# SmartMatrix_V1.net
KiCad netlist of a schematic drawn in EAGLE
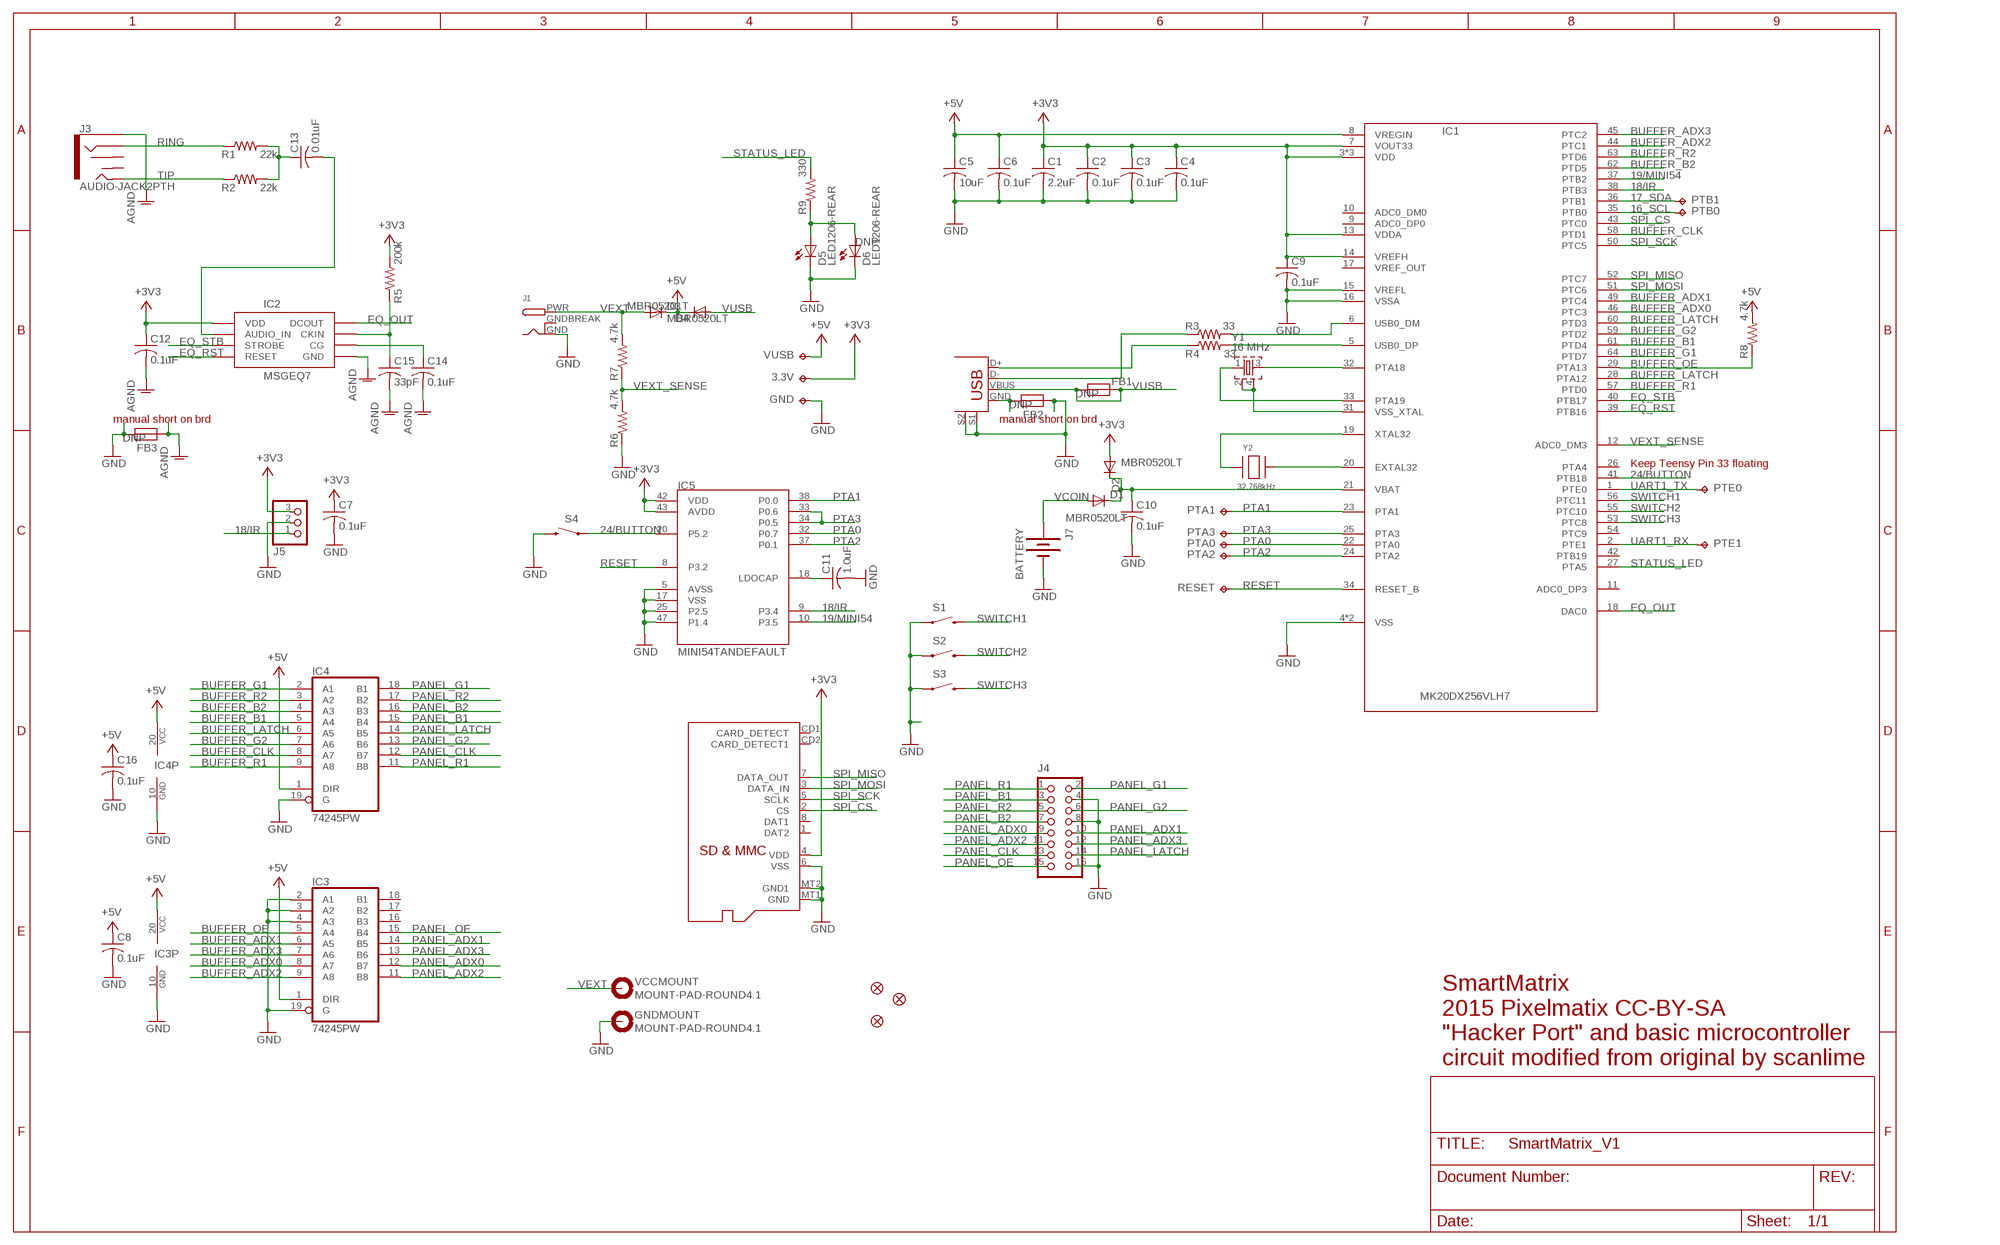
[diagram p0: schematic, sheet 1]

(export (version "E")
  (design (tool "Eeschema 10.0.6"))
  (components
    (comp (ref "3.3V")
      (value "TPTP18SQ")
      (footprint "eagle-import:TP18SQ")
      (libsource (lib "eagle-import") (part "TPTP18SQ"))
    )
    (comp (ref "C1")
      (value "2.2uF")
      (footprint "eagle-import:0805")
      (fields (field (name "PARTNO") "CAP CER 2.2UF 10V 10% X7R 0805"))
      (libsource (lib "eagle-import") (part "C-US0805/NO-OUTLINE"))
    )
    (comp (ref "C2")
      (value "0.1uF")
      (footprint "eagle-import:0805")
      (fields (field (name "PARTNO") "CAP CER 0.1UF 10V 10% X7R 0805"))
      (libsource (lib "eagle-import") (part "C-US0805/NO-OUTLINE"))
    )
    (comp (ref "C3")
      (value "0.1uF")
      (footprint "eagle-import:0805")
      (fields (field (name "PARTNO") "CAP CER 0.1UF 10V 10% X7R 0805"))
      (libsource (lib "eagle-import") (part "C-US0805/NO-OUTLINE"))
    )
    (comp (ref "C4")
      (value "0.1uF")
      (footprint "eagle-import:0805")
      (fields (field (name "PARTNO") "CAP CER 0.1UF 10V 10% X7R 0805"))
      (libsource (lib "eagle-import") (part "C-US0805/NO-OUTLINE"))
    )
    (comp (ref "C5")
      (value "10uF")
      (footprint "eagle-import:0805")
      (fields (field (name "PARTNO") "CAP CER 10UF 10V 10% X5R 0805"))
      (libsource (lib "eagle-import") (part "C-US0805/NO-OUTLINE"))
    )
    (comp (ref "C6")
      (value "0.1uF")
      (footprint "eagle-import:0805")
      (fields (field (name "PARTNO") "CAP CER 0.1UF 10V 10% X7R 0805"))
      (libsource (lib "eagle-import") (part "C-US0805/NO-OUTLINE"))
    )
    (comp (ref "C7")
      (value "0.1uF")
      (footprint "eagle-import:0805")
      (fields (field (name "PARTNO") "CAP CER 0.1UF 10V 10% X7R 0805"))
      (libsource (lib "eagle-import") (part "C-US0805/NO-OUTLINE"))
    )
    (comp (ref "C8")
      (value "0.1uF")
      (footprint "eagle-import:0805")
      (fields (field (name "PARTNO") "CAP CER 0.1UF 10V 10% X7R 0805"))
      (libsource (lib "eagle-import") (part "C-US0805/NO-OUTLINE"))
    )
    (comp (ref "C9")
      (value "0.1uF")
      (footprint "eagle-import:0805")
      (fields (field (name "PARTNO") "CAP CER 0.1UF 10V 10% X7R 0805"))
      (libsource (lib "eagle-import") (part "C-US0805/NO-OUTLINE"))
    )
    (comp (ref "C10")
      (value "0.1uF")
      (footprint "eagle-import:0805")
      (fields (field (name "PARTNO") "CAP CER 0.1UF 10V 10% X7R 0805"))
      (libsource (lib "eagle-import") (part "C-US0805/NO-OUTLINE"))
    )
    (comp (ref "C11")
      (value "1.0uF")
      (footprint "eagle-import:0805")
      (fields (field (name "PARTNO") "CAP CER 1UF 10V X7R 0805"))
      (libsource (lib "eagle-import") (part "C-US0805/NO-OUTLINE"))
    )
    (comp (ref "C12")
      (value "0.1uF")
      (footprint "eagle-import:0805")
      (fields (field (name "PARTNO") "CAP CER 0.1UF 10V 10% X7R 0805"))
      (libsource (lib "eagle-import") (part "C-US0805/NO-OUTLINE"))
    )
    (comp (ref "C13")
      (value "0.01uF")
      (footprint "eagle-import:0805")
      (fields (field (name "PARTNO") "CAP CER 10000PF 50V 10% X7R 0805"))
      (libsource (lib "eagle-import") (part "C-US0805/NO-OUTLINE"))
    )
    (comp (ref "C14")
      (value "0.1uF")
      (footprint "eagle-import:0805")
      (fields (field (name "PARTNO") "CAP CER 0.1UF 10V 10% X7R 0805"))
      (libsource (lib "eagle-import") (part "C-US0805/NO-OUTLINE"))
    )
    (comp (ref "C15")
      (value "33pF")
      (footprint "eagle-import:0805")
      (fields (field (name "PARTNO") "CAP CER 33PF 50V 5% NP0 0805"))
      (libsource (lib "eagle-import") (part "C-US0805/NO-OUTLINE"))
    )
    (comp (ref "C16")
      (value "0.1uF")
      (footprint "eagle-import:0805")
      (fields (field (name "PARTNO") "CAP CER 0.1UF 10V 10% X7R 0805"))
      (libsource (lib "eagle-import") (part "C-US0805/NO-OUTLINE"))
    )
    (comp (ref "D1")
      (value "MBR0520LT")
      (footprint "eagle-import:SOD123")
      (fields (field (name "PARTNO") "MBR0560-TP"))
      (libsource (lib "eagle-import") (part "MBR0520LT"))
    )
    (comp (ref "D2")
      (value "MBR0520LT")
      (footprint "eagle-import:SOD123")
      (fields (field (name "PARTNO") "MBR0560-TP"))
      (libsource (lib "eagle-import") (part "MBR0520LT"))
    )
    (comp (ref "D3")
      (value "MBR0520LT")
      (footprint "eagle-import:SOD123")
      (fields (field (name "PARTNO") "MBR0560-TP"))
      (libsource (lib "eagle-import") (part "MBR0520LT"))
    )
    (comp (ref "D4")
      (value "MBR0520LT")
      (footprint "eagle-import:SOD123")
      (fields (field (name "PARTNO") "MBR0560-TP"))
      (libsource (lib "eagle-import") (part "MBR0520LT"))
    )
    (comp (ref "D5")
      (value "LED1206-REAR")
      (footprint "eagle-import:LED-REARENTRY")
      (fields (field (name "PARTNO") "APTR3216YC"))
      (libsource (lib "eagle-import") (part "LED1206-REAR"))
    )
    (comp (ref "D6")
      (value "LED1206-REAR")
      (footprint "eagle-import:LED-REARENTRY")
      (libsource (lib "eagle-import") (part "LED1206-REAR"))
    )
    (comp (ref "FB1")
      (value "FB0805/NO-OUTLINE")
      (footprint "eagle-import:0805")
      (fields (field (name "PARTNO") "RES SMD 0.0 OHM JUMPER 1/8W 0805"))
      (libsource (lib "eagle-import") (part "FB0805/NO-OUTLINE"))
    )
    (comp (ref "FB2")
      (value "FB0805/NO-OUTLINE")
      (footprint "eagle-import:0805")
      (fields (field (name "PARTNO") "RES SMD 0.0 OHM JUMPER 1/8W 0805"))
      (libsource (lib "eagle-import") (part "FB0805/NO-OUTLINE"))
    )
    (comp (ref "FB3")
      (value "FB0805/NO-OUTLINE")
      (footprint "eagle-import:0805")
      (fields (field (name "PARTNO") "RES SMD 0.0 OHM JUMPER 1/8W 0805"))
      (libsource (lib "eagle-import") (part "FB0805/NO-OUTLINE"))
    )
    (comp (ref "FID1")
      (value "FIDUCIAL\"\"")
      (footprint "eagle-import:FIDUCIAL_1MM")
      (libsource (lib "eagle-import") (part "FIDUCIAL{dblquote}{dblquote}"))
    )
    (comp (ref "FID2")
      (value "FIDUCIAL\"\"")
      (footprint "eagle-import:FIDUCIAL_1MM")
      (libsource (lib "eagle-import") (part "FIDUCIAL{dblquote}{dblquote}"))
    )
    (comp (ref "FID3")
      (value "FIDUCIAL\"\"")
      (footprint "eagle-import:FIDUCIAL_1MM")
      (libsource (lib "eagle-import") (part "FIDUCIAL{dblquote}{dblquote}"))
    )
    (comp (ref "GND")
      (value "TPTP18SQ")
      (footprint "eagle-import:TP18SQ")
      (libsource (lib "eagle-import") (part "TPTP18SQ"))
    )
    (comp (ref "GNDMOUNT")
      (value "MOUNT-PAD-ROUND4.1")
      (footprint "eagle-import:4,1-PAD")
      (libsource (lib "eagle-import") (part "MOUNT-PAD-ROUND4.1"))
    )
    (comp (ref "IC1")
      (value "MK20DX256VLH7")
      (footprint "eagle-import:MK20DX256VLH7")
      (libsource (lib "eagle-import") (part "MK20DX256VLH7"))
    )
    (comp (ref "IC2")
      (value "MSGEQ7SOIC")
      (footprint "eagle-import:SOIC8")
      (fields (field (name "PARTNO") "MSGEQ7N"))
      (libsource (lib "eagle-import") (part "MSGEQ7SOIC"))
    )
    (comp (ref "IC3")
      (value "74245PW")
      (footprint "eagle-import:TSSOP-20")
      (fields (field (name "PARTNO") "SN74AHCT245PWR"))
      (libsource (lib "eagle-import") (part "74245PW"))
    )
    (comp (ref "IC4")
      (value "74245PW")
      (footprint "eagle-import:TSSOP-20")
      (fields (field (name "PARTNO") "SN74AHCT245PWR"))
      (libsource (lib "eagle-import") (part "74245PW"))
    )
    (comp (ref "IC5")
      (value "MINI54TANDEFAULT")
      (footprint "eagle-import:QFP50P900X900X160-48N")
      (libsource (lib "eagle-import") (part "MINI54TANDEFAULT"))
    )
    (comp (ref "J1")
      (value "DCBARRELPTH")
      (footprint "eagle-import:DCJACK_2MM_PTH")
      (fields (field (name "PARTNO") "PJ-002AH"))
      (libsource (lib "eagle-import") (part "DCBARRELPTH"))
    )
    (comp (ref "J2")
      (value "USB+SHIELD")
      (footprint "eagle-import:USB-B-PTH")
      (fields (field (name "PARTNO") "E8144-B02022-L"))
      (libsource (lib "eagle-import") (part "USB+SHIELD"))
    )
    (comp (ref "J3")
      (value "AUDIO-JACK2PTH")
      (footprint "eagle-import:AUDIO-JACK")
      (fields (field (name "PARTNO") "SJ1-3553NG"))
      (libsource (lib "eagle-import") (part "AUDIO-JACK2PTH"))
    )
    (comp (ref "J4")
      (value "CON_HEADER_2X08NOA")
      (footprint "eagle-import:2X08-NOA")
      (fields (field (name "PARTNO") "11149"))
      (libsource (lib "eagle-import") (part "CON_HEADER_2X08NOA"))
    )
    (comp (ref "J5")
      (value "CON_HEADER_1X03SMD/90-NOA")
      (footprint "eagle-import:1X03-SMD_90-NOA")
      (fields (field (name "PARTNO") "11182"))
      (libsource (lib "eagle-import") (part "CON_HEADER_1X03SMD/90-NOA"))
    )
    (comp (ref "J6")
      (value "MICROSD")
      (footprint "eagle-import:MICROSD")
      (fields (field (name "PARTNO") "101-00660-68-6"))
      (libsource (lib "eagle-import") (part "MICROSD"))
    )
    (comp (ref "J7")
      (value "BATTERY")
      (footprint "eagle-import:BU2032-SM")
      (fields (field (name "PARTNO") "05581"))
      (libsource (lib "eagle-import") (part "BATTERY"))
    )
    (comp (ref "PTA0")
      (value "TPTP18SQ")
      (footprint "eagle-import:TP18SQ")
      (libsource (lib "eagle-import") (part "TPTP18SQ"))
    )
    (comp (ref "PTA1")
      (value "TPTP18SQ")
      (footprint "eagle-import:TP18SQ")
      (libsource (lib "eagle-import") (part "TPTP18SQ"))
    )
    (comp (ref "PTA2")
      (value "TPTP18SQ")
      (footprint "eagle-import:TP18SQ")
      (libsource (lib "eagle-import") (part "TPTP18SQ"))
    )
    (comp (ref "PTA3")
      (value "TPTP18SQ")
      (footprint "eagle-import:TP18SQ")
      (libsource (lib "eagle-import") (part "TPTP18SQ"))
    )
    (comp (ref "PTB0")
      (value "TPTP18SQ")
      (footprint "eagle-import:TP18SQ")
      (libsource (lib "eagle-import") (part "TPTP18SQ"))
    )
    (comp (ref "PTB1")
      (value "TPTP18SQ")
      (footprint "eagle-import:TP18SQ")
      (libsource (lib "eagle-import") (part "TPTP18SQ"))
    )
    (comp (ref "PTE0")
      (value "TPTP18SQ")
      (footprint "eagle-import:TP18SQ")
      (libsource (lib "eagle-import") (part "TPTP18SQ"))
    )
    (comp (ref "PTE1")
      (value "TPTP18SQ")
      (footprint "eagle-import:TP18SQ")
      (libsource (lib "eagle-import") (part "TPTP18SQ"))
    )
    (comp (ref "R1")
      (value "22k")
      (footprint "eagle-import:0805")
      (fields (field (name "PARTNO") "RES SMD 22K OHM 5% 1/8W 0805"))
      (libsource (lib "eagle-import") (part "R-US_0805/NO-OUTLINE"))
    )
    (comp (ref "R2")
      (value "22k")
      (footprint "eagle-import:0805")
      (fields (field (name "PARTNO") "RES SMD 22K OHM 5% 1/8W 0805"))
      (libsource (lib "eagle-import") (part "R-US_0805/NO-OUTLINE"))
    )
    (comp (ref "R3")
      (value "33")
      (footprint "eagle-import:0805")
      (fields (field (name "PARTNO") "RES 33 OHM 1/8W 5% 0805 SMD"))
      (libsource (lib "eagle-import") (part "R-US_0805/NO-OUTLINE"))
    )
    (comp (ref "R4")
      (value "33")
      (footprint "eagle-import:0805")
      (fields (field (name "PARTNO") "RES 33 OHM 1/8W 5% 0805 SMD"))
      (libsource (lib "eagle-import") (part "R-US_0805/NO-OUTLINE"))
    )
    (comp (ref "R5")
      (value "200k")
      (footprint "eagle-import:0805")
      (fields (field (name "PARTNO") "RES SMD 200K OHM 5% 1/8W 0805"))
      (libsource (lib "eagle-import") (part "R-US_0805/NO-OUTLINE"))
    )
    (comp (ref "R6")
      (value "4.7k")
      (footprint "eagle-import:0805")
      (fields (field (name "PARTNO") "RES SMD 4.7K OHM 5% 1/8W 0805"))
      (libsource (lib "eagle-import") (part "R-US_0805/NO-OUTLINE"))
    )
    (comp (ref "R7")
      (value "4.7k")
      (footprint "eagle-import:0805")
      (fields (field (name "PARTNO") "RES SMD 4.7K OHM 5% 1/8W 0805"))
      (libsource (lib "eagle-import") (part "R-US_0805/NO-OUTLINE"))
    )
    (comp (ref "R8")
      (value "4.7k")
      (footprint "eagle-import:0805")
      (fields (field (name "PARTNO") "RES SMD 4.7K OHM 5% 1/8W 0805"))
      (libsource (lib "eagle-import") (part "R-US_0805/NO-OUTLINE"))
    )
    (comp (ref "R9")
      (value "330")
      (footprint "eagle-import:0805")
      (fields (field (name "PARTNO") "RES SMD 330 OHM 5% 1/8W 0805"))
      (libsource (lib "eagle-import") (part "R-US_0805/NO-OUTLINE"))
    )
    (comp (ref "RESET")
      (value "TPTP18SQ")
      (footprint "eagle-import:TP18SQ")
      (libsource (lib "eagle-import") (part "TPTP18SQ"))
    )
    (comp (ref "S1")
      (value "SWITCH-MOMENTARY-2PTH")
      (footprint "eagle-import:TACTILE-PTH")
      (libsource (lib "eagle-import") (part "SWITCH-MOMENTARY-2PTH"))
    )
    (comp (ref "S2")
      (value "SWITCH-MOMENTARY-2PTH")
      (footprint "eagle-import:TACTILE-PTH")
      (libsource (lib "eagle-import") (part "SWITCH-MOMENTARY-2PTH"))
    )
    (comp (ref "S3")
      (value "SWITCH-MOMENTARY-2PTH")
      (footprint "eagle-import:TACTILE-PTH")
      (libsource (lib "eagle-import") (part "SWITCH-MOMENTARY-2PTH"))
    )
    (comp (ref "S4")
      (value "SWITCH-MOMENTARY-2PTH")
      (footprint "eagle-import:TACTILE-PTH")
      (libsource (lib "eagle-import") (part "SWITCH-MOMENTARY-2PTH"))
    )
    (comp (ref "VCCMOUNT")
      (value "MOUNT-PAD-ROUND4.1")
      (footprint "eagle-import:4,1-PAD")
      (libsource (lib "eagle-import") (part "MOUNT-PAD-ROUND4.1"))
    )
    (comp (ref "VUSB")
      (value "TPTP18SQ")
      (footprint "eagle-import:TP18SQ")
      (libsource (lib "eagle-import") (part "TPTP18SQ"))
    )
    (comp (ref "Y1")
      (value "16 MHz")
      (footprint "eagle-import:TSX-3225")
      (fields (field (name "PARTNO") "TSX-3225 16.0000MF09Z-AC3"))
      (libsource (lib "eagle-import") (part "TSX-32250"))
    )
    (comp (ref "Y2")
      (value "32.768kHz")
      (footprint "eagle-import:XTAL3215")
      (fields (field (name "PARTNO") "9HT10-32.768KDZF-T"))
      (libsource (lib "eagle-import") (part "XTAL-3.2X1.5"))
    )
  )
  (nets
    (net (code "1") (name "+3V3") (class "Default")
      (node (ref "3.3V") (pin "TP") (pinfunction "TP_TP") (pintype "input"))
      (node (ref "C1") (pin "1") (pinfunction "1_1") (pintype "passive"))
      (node (ref "C12") (pin "1") (pinfunction "1_1") (pintype "passive"))
      (node (ref "C2") (pin "1") (pinfunction "1_1") (pintype "passive"))
      (node (ref "C3") (pin "1") (pinfunction "1_1") (pintype "passive"))
      (node (ref "C4") (pin "1") (pinfunction "1_1") (pintype "passive"))
      (node (ref "C7") (pin "1") (pinfunction "1_1") (pintype "passive"))
      (node (ref "C9") (pin "1") (pinfunction "1_1") (pintype "passive"))
      (node (ref "D2") (pin "A") (pinfunction "A_A") (pintype "passive"))
      (node (ref "IC1") (pin "13") (pinfunction "VDDA_13") (pintype "bidirectional"))
      (node (ref "IC1") (pin "14") (pinfunction "VREFH_14") (pintype "bidirectional"))
      (node (ref "IC1") (pin "3") (pinfunction "VDD_3") (pintype "bidirectional"))
      (node (ref "IC1") (pin "30") (pinfunction "VDD_30") (pintype "bidirectional"))
      (node (ref "IC1") (pin "48") (pinfunction "VDD_48") (pintype "bidirectional"))
      (node (ref "IC1") (pin "7") (pinfunction "VOUT33_7") (pintype "bidirectional"))
      (node (ref "IC2") (pin "1") (pinfunction "VDD_1") (pintype "input"))
      (node (ref "IC5") (pin "42") (pinfunction "VDD_42") (pintype "bidirectional"))
      (node (ref "IC5") (pin "43") (pinfunction "AVDD_43") (pintype "bidirectional"))
      (node (ref "J5") (pin "3") (pinfunction "3_3") (pintype "passive"))
      (node (ref "J6") (pin "4") (pinfunction "VDD_4") (pintype "power_in"))
      (node (ref "R5") (pin "2") (pinfunction "2_2") (pintype "passive"))
    )
    (net (code "2") (name "+5V") (class "Default")
      (node (ref "C16") (pin "1") (pinfunction "1_1") (pintype "passive"))
      (node (ref "C5") (pin "1") (pinfunction "1_1") (pintype "passive"))
      (node (ref "C6") (pin "1") (pinfunction "1_1") (pintype "passive"))
      (node (ref "C8") (pin "1") (pinfunction "1_1") (pintype "passive"))
      (node (ref "D3") (pin "C") (pinfunction "C_C") (pintype "passive"))
      (node (ref "D4") (pin "C") (pinfunction "C_C") (pintype "passive"))
      (node (ref "IC1") (pin "8") (pinfunction "VREGIN_8") (pintype "bidirectional"))
      (node (ref "IC3") (pin "1") (pinfunction "DIR_1") (pintype "input"))
      (node (ref "IC3") (pin "20") (pinfunction "VCC_20") (pintype "power_in"))
      (node (ref "IC4") (pin "1") (pinfunction "DIR_1") (pintype "input"))
      (node (ref "IC4") (pin "20") (pinfunction "VCC_20") (pintype "power_in"))
      (node (ref "R8") (pin "2") (pinfunction "2_2") (pintype "passive"))
      (node (ref "VUSB") (pin "TP") (pinfunction "TP_TP") (pintype "input"))
    )
    (net (code "3") (name "/16_SCL") (class "Default")
      (node (ref "IC1") (pin "35") (pinfunction "PTB0_35") (pintype "bidirectional"))
      (node (ref "PTB0") (pin "TP") (pinfunction "TP_TP") (pintype "input"))
    )
    (net (code "4") (name "/17_SDA") (class "Default")
      (node (ref "IC1") (pin "36") (pinfunction "PTB1_36") (pintype "bidirectional"))
      (node (ref "PTB1") (pin "TP") (pinfunction "TP_TP") (pintype "input"))
    )
    (net (code "5") (name "/18{slash}IR") (class "Default")
      (node (ref "IC1") (pin "38") (pinfunction "PTB3_38") (pintype "bidirectional"))
      (node (ref "IC5") (pin "9") (pinfunction "P3.4_9") (pintype "bidirectional"))
      (node (ref "J5") (pin "1") (pinfunction "1_1") (pintype "passive"))
    )
    (net (code "6") (name "/19{slash}MINI54") (class "Default")
      (node (ref "IC1") (pin "37") (pinfunction "PTB2_37") (pintype "bidirectional"))
      (node (ref "IC5") (pin "10") (pinfunction "P3.5_10") (pintype "bidirectional"))
    )
    (net (code "7") (name "/24{slash}BUTTON") (class "Default")
      (node (ref "IC1") (pin "41") (pinfunction "PTB18_41") (pintype "bidirectional"))
      (node (ref "IC5") (pin "20") (pinfunction "P5.2_20") (pintype "bidirectional"))
      (node (ref "S4") (pin "1") (pinfunction "1_1") (pintype "passive"))
    )
    (net (code "8") (name "/BUFFER_ADX0") (class "Default")
      (node (ref "IC1") (pin "46") (pinfunction "PTC3_46") (pintype "bidirectional"))
      (node (ref "IC3") (pin "8") (pinfunction "A7_8") (pintype "bidirectional"))
    )
    (net (code "9") (name "/BUFFER_ADX1") (class "Default")
      (node (ref "IC1") (pin "49") (pinfunction "PTC4_49") (pintype "bidirectional"))
      (node (ref "IC3") (pin "6") (pinfunction "A5_6") (pintype "bidirectional"))
    )
    (net (code "10") (name "/BUFFER_ADX2") (class "Default")
      (node (ref "IC1") (pin "44") (pinfunction "PTC1_44") (pintype "bidirectional"))
      (node (ref "IC3") (pin "9") (pinfunction "A8_9") (pintype "bidirectional"))
    )
    (net (code "11") (name "/BUFFER_ADX3") (class "Default")
      (node (ref "IC1") (pin "45") (pinfunction "PTC2_45") (pintype "bidirectional"))
      (node (ref "IC3") (pin "7") (pinfunction "A6_7") (pintype "bidirectional"))
    )
    (net (code "12") (name "/BUFFER_B1") (class "Default")
      (node (ref "IC1") (pin "61") (pinfunction "PTD4_61") (pintype "bidirectional"))
      (node (ref "IC4") (pin "5") (pinfunction "A4_5") (pintype "bidirectional"))
    )
    (net (code "13") (name "/BUFFER_B2") (class "Default")
      (node (ref "IC1") (pin "62") (pinfunction "PTD5_62") (pintype "bidirectional"))
      (node (ref "IC4") (pin "4") (pinfunction "A3_4") (pintype "bidirectional"))
    )
    (net (code "14") (name "/BUFFER_CLK") (class "Default")
      (node (ref "IC1") (pin "58") (pinfunction "PTD1_58") (pintype "bidirectional"))
      (node (ref "IC4") (pin "8") (pinfunction "A7_8") (pintype "bidirectional"))
    )
    (net (code "15") (name "/BUFFER_G1") (class "Default")
      (node (ref "IC1") (pin "64") (pinfunction "PTD7_64") (pintype "bidirectional"))
      (node (ref "IC4") (pin "2") (pinfunction "A1_2") (pintype "bidirectional"))
    )
    (net (code "16") (name "/BUFFER_G2") (class "Default")
      (node (ref "IC1") (pin "59") (pinfunction "PTD2_59") (pintype "bidirectional"))
      (node (ref "IC4") (pin "7") (pinfunction "A6_7") (pintype "bidirectional"))
    )
    (net (code "17") (name "/BUFFER_LATCH") (class "Default")
      (node (ref "IC1") (pin "28") (pinfunction "PTA12_28") (pintype "bidirectional"))
      (node (ref "IC1") (pin "60") (pinfunction "PTD3_60") (pintype "bidirectional"))
      (node (ref "IC4") (pin "6") (pinfunction "A5_6") (pintype "bidirectional"))
    )
    (net (code "18") (name "/BUFFER_OE") (class "Default")
      (node (ref "IC1") (pin "29") (pinfunction "PTA13_29") (pintype "bidirectional"))
      (node (ref "IC3") (pin "5") (pinfunction "A4_5") (pintype "bidirectional"))
      (node (ref "R8") (pin "1") (pinfunction "1_1") (pintype "passive"))
    )
    (net (code "19") (name "/BUFFER_R1") (class "Default")
      (node (ref "IC1") (pin "57") (pinfunction "PTD0_57") (pintype "bidirectional"))
      (node (ref "IC4") (pin "9") (pinfunction "A8_9") (pintype "bidirectional"))
    )
    (net (code "20") (name "/BUFFER_R2") (class "Default")
      (node (ref "IC1") (pin "63") (pinfunction "PTD6_63") (pintype "bidirectional"))
      (node (ref "IC4") (pin "3") (pinfunction "A2_3") (pintype "bidirectional"))
    )
    (net (code "21") (name "/EQ_OUT") (class "Default")
      (node (ref "IC1") (pin "18") (pinfunction "DAC0_18") (pintype "bidirectional"))
      (node (ref "IC2") (pin "3") (pinfunction "DCOUT_3") (pintype "bidirectional"))
    )
    (net (code "22") (name "/EQ_RST") (class "Default")
      (node (ref "IC1") (pin "39") (pinfunction "PTB16_39") (pintype "bidirectional"))
      (node (ref "IC2") (pin "7") (pinfunction "RESET_7") (pintype "input"))
    )
    (net (code "23") (name "/EQ_STB") (class "Default")
      (node (ref "IC1") (pin "40") (pinfunction "PTB17_40") (pintype "bidirectional"))
      (node (ref "IC2") (pin "4") (pinfunction "STROBE_4") (pintype "input"))
    )
    (net (code "24") (name "/GNDBREAK") (class "Default")
      (node (ref "J1") (pin "GNDBREAK") (pinfunction "GNDBREAK_GNDBREAK") (pintype "power_in"))
    )
    (net (code "25") (name "/PANEL_ADX0") (class "Default")
      (node (ref "IC3") (pin "12") (pinfunction "B7_12") (pintype "bidirectional"))
      (node (ref "J4") (pin "9") (pinfunction "9_9") (pintype "passive"))
    )
    (net (code "26") (name "/PANEL_ADX1") (class "Default")
      (node (ref "IC3") (pin "14") (pinfunction "B5_14") (pintype "bidirectional"))
      (node (ref "J4") (pin "10") (pinfunction "10_10") (pintype "passive"))
    )
    (net (code "27") (name "/PANEL_ADX2") (class "Default")
      (node (ref "IC3") (pin "11") (pinfunction "B8_11") (pintype "bidirectional"))
      (node (ref "J4") (pin "11") (pinfunction "11_11") (pintype "passive"))
    )
    (net (code "28") (name "/PANEL_ADX3") (class "Default")
      (node (ref "IC3") (pin "13") (pinfunction "B6_13") (pintype "bidirectional"))
      (node (ref "J4") (pin "12") (pinfunction "12_12") (pintype "passive"))
    )
    (net (code "29") (name "/PANEL_B1") (class "Default")
      (node (ref "IC4") (pin "15") (pinfunction "B4_15") (pintype "bidirectional"))
      (node (ref "J4") (pin "3") (pinfunction "3_3") (pintype "passive"))
    )
    (net (code "30") (name "/PANEL_B2") (class "Default")
      (node (ref "IC4") (pin "16") (pinfunction "B3_16") (pintype "bidirectional"))
      (node (ref "J4") (pin "7") (pinfunction "7_7") (pintype "passive"))
    )
    (net (code "31") (name "/PANEL_CLK") (class "Default")
      (node (ref "IC4") (pin "12") (pinfunction "B7_12") (pintype "bidirectional"))
      (node (ref "J4") (pin "13") (pinfunction "13_13") (pintype "passive"))
    )
    (net (code "32") (name "/PANEL_G1") (class "Default")
      (node (ref "IC4") (pin "18") (pinfunction "B1_18") (pintype "bidirectional"))
      (node (ref "J4") (pin "2") (pinfunction "2_2") (pintype "passive"))
    )
    (net (code "33") (name "/PANEL_G2") (class "Default")
      (node (ref "IC4") (pin "13") (pinfunction "B6_13") (pintype "bidirectional"))
      (node (ref "J4") (pin "6") (pinfunction "6_6") (pintype "passive"))
    )
    (net (code "34") (name "/PANEL_LATCH") (class "Default")
      (node (ref "IC4") (pin "14") (pinfunction "B5_14") (pintype "bidirectional"))
      (node (ref "J4") (pin "14") (pinfunction "14_14") (pintype "passive"))
    )
    (net (code "35") (name "/PANEL_OE") (class "Default")
      (node (ref "IC3") (pin "15") (pinfunction "B4_15") (pintype "bidirectional"))
      (node (ref "J4") (pin "15") (pinfunction "15_15") (pintype "passive"))
    )
    (net (code "36") (name "/PANEL_R1") (class "Default")
      (node (ref "IC4") (pin "11") (pinfunction "B8_11") (pintype "bidirectional"))
      (node (ref "J4") (pin "1") (pinfunction "1_1") (pintype "passive"))
    )
    (net (code "37") (name "/PANEL_R2") (class "Default")
      (node (ref "IC4") (pin "17") (pinfunction "B2_17") (pintype "bidirectional"))
      (node (ref "J4") (pin "5") (pinfunction "5_5") (pintype "passive"))
    )
    (net (code "38") (name "/PTA0") (class "Default")
      (node (ref "IC1") (pin "22") (pinfunction "PTA0_22") (pintype "bidirectional"))
      (node (ref "IC5") (pin "32") (pinfunction "P0.7_32") (pintype "bidirectional"))
      (node (ref "PTA0") (pin "TP") (pinfunction "TP_TP") (pintype "input"))
    )
    (net (code "39") (name "/PTA1") (class "Default")
      (node (ref "IC1") (pin "23") (pinfunction "PTA1_23") (pintype "bidirectional"))
      (node (ref "IC5") (pin "38") (pinfunction "P0.0_38") (pintype "bidirectional"))
      (node (ref "PTA1") (pin "TP") (pinfunction "TP_TP") (pintype "input"))
    )
    (net (code "40") (name "/PTA2") (class "Default")
      (node (ref "IC1") (pin "24") (pinfunction "PTA2_24") (pintype "bidirectional"))
      (node (ref "IC5") (pin "37") (pinfunction "P0.1_37") (pintype "bidirectional"))
      (node (ref "PTA2") (pin "TP") (pinfunction "TP_TP") (pintype "input"))
    )
    (net (code "41") (name "/PTA3") (class "Default")
      (node (ref "IC1") (pin "25") (pinfunction "PTA3_25") (pintype "bidirectional"))
      (node (ref "IC5") (pin "33") (pinfunction "P0.6_33") (pintype "bidirectional"))
      (node (ref "IC5") (pin "34") (pinfunction "P0.5_34") (pintype "bidirectional"))
      (node (ref "PTA3") (pin "TP") (pinfunction "TP_TP") (pintype "input"))
    )
    (net (code "42") (name "/RESET") (class "Default")
      (node (ref "IC1") (pin "34") (pinfunction "RESET_B_34") (pintype "bidirectional"))
      (node (ref "IC5") (pin "8") (pinfunction "P3.2_8") (pintype "bidirectional"))
      (node (ref "RESET") (pin "TP") (pinfunction "TP_TP") (pintype "input"))
    )
    (net (code "43") (name "/RING") (class "Default")
      (node (ref "J3") (pin "RING") (pinfunction "RING_RING") (pintype "bidirectional"))
      (node (ref "R1") (pin "1") (pinfunction "1_1") (pintype "passive"))
    )
    (net (code "44") (name "/SPI_CS") (class "Default")
      (node (ref "IC1") (pin "43") (pinfunction "PTC0_43") (pintype "bidirectional"))
      (node (ref "J6") (pin "2") (pinfunction "CS_2") (pintype "input"))
    )
    (net (code "45") (name "/SPI_MISO") (class "Default")
      (node (ref "IC1") (pin "52") (pinfunction "PTC7_52") (pintype "bidirectional"))
      (node (ref "J6") (pin "7") (pinfunction "DATA_OUT_7") (pintype "output"))
    )
    (net (code "46") (name "/SPI_MOSI") (class "Default")
      (node (ref "IC1") (pin "51") (pinfunction "PTC6_51") (pintype "bidirectional"))
      (node (ref "J6") (pin "3") (pinfunction "DATA_IN_3") (pintype "input"))
    )
    (net (code "47") (name "/SPI_SCK") (class "Default")
      (node (ref "IC1") (pin "50") (pinfunction "PTC5_50") (pintype "bidirectional"))
      (node (ref "J6") (pin "5") (pinfunction "SCLK_5") (pintype "input"))
    )
    (net (code "48") (name "/STATUS_LED") (class "Default")
      (node (ref "IC1") (pin "27") (pinfunction "PTA5_27") (pintype "bidirectional"))
      (node (ref "R9") (pin "2") (pinfunction "2_2") (pintype "passive"))
    )
    (net (code "49") (name "/SWITCH1") (class "Default")
      (node (ref "IC1") (pin "56") (pinfunction "PTC11_56") (pintype "bidirectional"))
      (node (ref "S1") (pin "3") (pinfunction "2_3") (pintype "passive"))
    )
    (net (code "50") (name "/SWITCH2") (class "Default")
      (node (ref "IC1") (pin "55") (pinfunction "PTC10_55") (pintype "bidirectional"))
      (node (ref "S2") (pin "3") (pinfunction "2_3") (pintype "passive"))
    )
    (net (code "51") (name "/SWITCH3") (class "Default")
      (node (ref "IC1") (pin "53") (pinfunction "PTC8_53") (pintype "bidirectional"))
      (node (ref "S3") (pin "3") (pinfunction "2_3") (pintype "passive"))
    )
    (net (code "52") (name "/TIP") (class "Default")
      (node (ref "J3") (pin "TIP") (pinfunction "TIP_TIP") (pintype "bidirectional"))
      (node (ref "R2") (pin "1") (pinfunction "1_1") (pintype "passive"))
    )
    (net (code "53") (name "/UART1_RX") (class "Default")
      (node (ref "IC1") (pin "2") (pinfunction "PTE1_2") (pintype "bidirectional"))
      (node (ref "PTE1") (pin "TP") (pinfunction "TP_TP") (pintype "input"))
    )
    (net (code "54") (name "/UART1_TX") (class "Default")
      (node (ref "IC1") (pin "1") (pinfunction "PTE0_1") (pintype "bidirectional"))
      (node (ref "PTE0") (pin "TP") (pinfunction "TP_TP") (pintype "input"))
    )
    (net (code "55") (name "/VCOIN") (class "Default")
      (node (ref "D1") (pin "A") (pinfunction "A_A") (pintype "passive"))
      (node (ref "J7") (pin "+") (pinfunction "+_+") (pintype "power_in"))
    )
    (net (code "56") (name "/VEXT") (class "Default")
      (node (ref "D3") (pin "A") (pinfunction "A_A") (pintype "passive"))
      (node (ref "J1") (pin "PWR") (pinfunction "PWR_PWR") (pintype "power_in"))
      (node (ref "R7") (pin "2") (pinfunction "2_2") (pintype "passive"))
      (node (ref "VCCMOUNT") (pin "B4,1") (pinfunction "MOUNT_B4,1") (pintype "passive"))
    )
    (net (code "57") (name "/VEXT_SENSE") (class "Default")
      (node (ref "IC1") (pin "12") (pinfunction "ADC0_DM3_12") (pintype "bidirectional"))
      (node (ref "R6") (pin "2") (pinfunction "2_2") (pintype "passive"))
      (node (ref "R7") (pin "1") (pinfunction "1_1") (pintype "passive"))
    )
    (net (code "58") (name "/VUSB") (class "Default")
      (node (ref "D4") (pin "A") (pinfunction "A_A") (pintype "passive"))
      (node (ref "FB1") (pin "1") (pinfunction "P$1_1") (pintype "bidirectional"))
      (node (ref "FB1") (pin "2") (pinfunction "P$2_2") (pintype "bidirectional"))
      (node (ref "J2") (pin "VBUS") (pinfunction "VBUS_VBUS") (pintype "bidirectional"))
    )
    (net (code "59") (name "AGND") (class "Default")
      (node (ref "C12") (pin "2") (pinfunction "2_2") (pintype "passive"))
      (node (ref "C14") (pin "2") (pinfunction "2_2") (pintype "passive"))
      (node (ref "C15") (pin "2") (pinfunction "2_2") (pintype "passive"))
      (node (ref "FB3") (pin "2") (pinfunction "P$2_2") (pintype "bidirectional"))
      (node (ref "IC2") (pin "2") (pinfunction "GND_2") (pintype "bidirectional"))
      (node (ref "J3") (pin "SLEEVE") (pinfunction "SLEEVE_SLEEVE") (pintype "bidirectional"))
    )
    (net (code "60") (name "GND") (class "Default")
      (node (ref "C1") (pin "2") (pinfunction "2_2") (pintype "passive"))
      (node (ref "C10") (pin "2") (pinfunction "2_2") (pintype "passive"))
      (node (ref "C11") (pin "2") (pinfunction "2_2") (pintype "passive"))
      (node (ref "C16") (pin "2") (pinfunction "2_2") (pintype "passive"))
      (node (ref "C2") (pin "2") (pinfunction "2_2") (pintype "passive"))
      (node (ref "C3") (pin "2") (pinfunction "2_2") (pintype "passive"))
      (node (ref "C4") (pin "2") (pinfunction "2_2") (pintype "passive"))
      (node (ref "C5") (pin "2") (pinfunction "2_2") (pintype "passive"))
      (node (ref "C6") (pin "2") (pinfunction "2_2") (pintype "passive"))
      (node (ref "C7") (pin "2") (pinfunction "2_2") (pintype "passive"))
      (node (ref "C8") (pin "2") (pinfunction "2_2") (pintype "passive"))
      (node (ref "C9") (pin "2") (pinfunction "2_2") (pintype "passive"))
      (node (ref "D5") (pin "-") (pinfunction "C_-") (pintype "passive"))
      (node (ref "D6") (pin "-") (pinfunction "C_-") (pintype "passive"))
      (node (ref "FB2") (pin "2") (pinfunction "P$2_2") (pintype "bidirectional"))
      (node (ref "FB3") (pin "1") (pinfunction "P$1_1") (pintype "bidirectional"))
      (node (ref "GND") (pin "TP") (pinfunction "TP_TP") (pintype "input"))
      (node (ref "GNDMOUNT") (pin "B4,1") (pinfunction "MOUNT_B4,1") (pintype "passive"))
      (node (ref "IC1") (pin "15") (pinfunction "VREFL_15") (pintype "bidirectional"))
      (node (ref "IC1") (pin "16") (pinfunction "VSSA_16") (pintype "bidirectional"))
      (node (ref "IC1") (pin "4") (pinfunction "VSS_4") (pintype "bidirectional"))
      (node (ref "IC1") (pin "47") (pinfunction "VSS_47") (pintype "bidirectional"))
      (node (ref "IC3") (pin "10") (pinfunction "GND_10") (pintype "power_in"))
      (node (ref "IC3") (pin "19") (pinfunction "G_19") (pintype "input"))
      (node (ref "IC3") (pin "2") (pinfunction "A1_2") (pintype "bidirectional"))
      (node (ref "IC3") (pin "3") (pinfunction "A2_3") (pintype "bidirectional"))
      (node (ref "IC3") (pin "4") (pinfunction "A3_4") (pintype "bidirectional"))
      (node (ref "IC4") (pin "10") (pinfunction "GND_10") (pintype "power_in"))
      (node (ref "IC4") (pin "19") (pinfunction "G_19") (pintype "input"))
      (node (ref "IC5") (pin "17") (pinfunction "VSS_17") (pintype "bidirectional"))
      (node (ref "IC5") (pin "25") (pinfunction "P2.5_25") (pintype "bidirectional"))
      (node (ref "IC5") (pin "47") (pinfunction "P1.4_47") (pintype "bidirectional"))
      (node (ref "IC5") (pin "5") (pinfunction "AVSS_5") (pintype "bidirectional"))
      (node (ref "J1") (pin "GND") (pinfunction "GND_GND") (pintype "power_in"))
      (node (ref "J2") (pin "S1") (pinfunction "P$1_S1") (pintype "bidirectional"))
      (node (ref "J2") (pin "S2") (pinfunction "P$2_S2") (pintype "bidirectional"))
      (node (ref "J4") (pin "16") (pinfunction "16_16") (pintype "passive"))
      (node (ref "J4") (pin "4") (pinfunction "4_4") (pintype "passive"))
      (node (ref "J4") (pin "8") (pinfunction "8_8") (pintype "passive"))
      (node (ref "J5") (pin "2") (pinfunction "2_2") (pintype "passive"))
      (node (ref "J6") (pin "6") (pinfunction "VSS_6") (pintype "power_in"))
      (node (ref "J6") (pin "MT1") (pinfunction "GND_MT1") (pintype "power_in"))
      (node (ref "J6") (pin "MT2") (pinfunction "GND1_MT2") (pintype "power_in"))
      (node (ref "J7") (pin "-") (pinfunction "-_-") (pintype "power_in"))
      (node (ref "R6") (pin "1") (pinfunction "1_1") (pintype "passive"))
      (node (ref "S1") (pin "1") (pinfunction "1_1") (pintype "passive"))
      (node (ref "S2") (pin "1") (pinfunction "1_1") (pintype "passive"))
      (node (ref "S3") (pin "1") (pinfunction "1_1") (pintype "passive"))
      (node (ref "S4") (pin "3") (pinfunction "2_3") (pintype "passive"))
    )
    (net (code "61") (name "Net-(C13-Pad1)") (class "Default")
      (node (ref "C13") (pin "1") (pinfunction "1_1") (pintype "passive"))
      (node (ref "R1") (pin "2") (pinfunction "2_2") (pintype "passive"))
      (node (ref "R2") (pin "2") (pinfunction "2_2") (pintype "passive"))
    )
    (net (code "62") (name "Net-(D5-A)") (class "Default")
      (node (ref "D5") (pin "+") (pinfunction "A_+") (pintype "passive"))
      (node (ref "D6") (pin "+") (pinfunction "A_+") (pintype "passive"))
      (node (ref "R9") (pin "1") (pinfunction "1_1") (pintype "passive"))
    )
    (net (code "63") (name "Net-(FB2-P$1)") (class "Default")
      (node (ref "FB2") (pin "1") (pinfunction "P$1_1") (pintype "bidirectional"))
      (node (ref "J2") (pin "GND") (pinfunction "GND_GND") (pintype "bidirectional"))
    )
    (net (code "64") (name "Net-(IC1-EXTAL32)") (class "Default")
      (node (ref "IC1") (pin "20") (pinfunction "EXTAL32_20") (pintype "bidirectional"))
      (node (ref "Y2") (pin "P$2") (pinfunction "P$2_P$2") (pintype "bidirectional"))
    )
    (net (code "65") (name "Net-(IC1-PTA18)") (class "Default")
      (node (ref "IC1") (pin "32") (pinfunction "PTA18_32") (pintype "bidirectional"))
      (node (ref "Y1") (pin "3") (pinfunction "3_3") (pintype "passive"))
    )
    (net (code "66") (name "Net-(IC1-PTA19)") (class "Default")
      (node (ref "IC1") (pin "33") (pinfunction "PTA19_33") (pintype "bidirectional"))
      (node (ref "Y1") (pin "1") (pinfunction "1_1") (pintype "passive"))
    )
    (net (code "67") (name "Net-(IC1-USB0_DM)") (class "Default")
      (node (ref "IC1") (pin "6") (pinfunction "USB0_DM_6") (pintype "bidirectional"))
      (node (ref "R3") (pin "2") (pinfunction "2_2") (pintype "passive"))
    )
    (net (code "68") (name "Net-(IC1-USB0_DP)") (class "Default")
      (node (ref "IC1") (pin "5") (pinfunction "USB0_DP_5") (pintype "bidirectional"))
      (node (ref "R4") (pin "2") (pinfunction "2_2") (pintype "passive"))
    )
    (net (code "69") (name "Net-(IC1-VBAT)") (class "Default")
      (node (ref "C10") (pin "1") (pinfunction "1_1") (pintype "passive"))
      (node (ref "D1") (pin "C") (pinfunction "C_C") (pintype "passive"))
      (node (ref "D2") (pin "C") (pinfunction "C_C") (pintype "passive"))
      (node (ref "IC1") (pin "21") (pinfunction "VBAT_21") (pintype "bidirectional"))
    )
    (net (code "70") (name "Net-(IC1-VSS_XTAL)") (class "Default")
      (node (ref "IC1") (pin "31") (pinfunction "VSS_XTAL_31") (pintype "bidirectional"))
      (node (ref "Y1") (pin "2") (pinfunction "2_2") (pintype "passive"))
      (node (ref "Y1") (pin "4") (pinfunction "4_4") (pintype "passive"))
    )
    (net (code "71") (name "Net-(IC1-XTAL32)") (class "Default")
      (node (ref "IC1") (pin "19") (pinfunction "XTAL32_19") (pintype "bidirectional"))
      (node (ref "Y2") (pin "P$1") (pinfunction "P$1_P$1") (pintype "bidirectional"))
    )
    (net (code "72") (name "Net-(IC2-AUDIO_IN)") (class "Default")
      (node (ref "C13") (pin "2") (pinfunction "2_2") (pintype "passive"))
      (node (ref "IC2") (pin "5") (pinfunction "AUDIO_IN_5") (pintype "input"))
    )
    (net (code "73") (name "Net-(IC2-CG)") (class "Default")
      (node (ref "C14") (pin "1") (pinfunction "1_1") (pintype "passive"))
      (node (ref "IC2") (pin "6") (pinfunction "CG_6") (pintype "bidirectional"))
    )
    (net (code "74") (name "Net-(IC2-CKIN)") (class "Default")
      (node (ref "C15") (pin "1") (pinfunction "1_1") (pintype "passive"))
      (node (ref "IC2") (pin "8") (pinfunction "CKIN_8") (pintype "bidirectional"))
      (node (ref "R5") (pin "1") (pinfunction "1_1") (pintype "passive"))
    )
    (net (code "75") (name "Net-(IC5-LDOCAP)") (class "Default")
      (node (ref "C11") (pin "1") (pinfunction "1_1") (pintype "passive"))
      (node (ref "IC5") (pin "18") (pinfunction "LDOCAP_18") (pintype "bidirectional"))
    )
    (net (code "76") (name "Net-(J2-PadD+)") (class "Default")
      (node (ref "J2") (pin "D+") (pinfunction "D+_D+") (pintype "bidirectional"))
      (node (ref "R4") (pin "1") (pinfunction "1_1") (pintype "passive"))
    )
    (net (code "77") (name "Net-(J2-PadD-)") (class "Default")
      (node (ref "J2") (pin "D-") (pinfunction "D-_D-") (pintype "bidirectional"))
      (node (ref "R3") (pin "1") (pinfunction "1_1") (pintype "passive"))
    )
    (net (code "78") (name "unconnected-(IC1-ADC0_DM0-Pad10)") (class "Default")
      (node (ref "IC1") (pin "10") (pinfunction "ADC0_DM0_10") (pintype "bidirectional"))
    )
    (net (code "79") (name "unconnected-(IC1-ADC0_DP0-Pad9)") (class "Default")
      (node (ref "IC1") (pin "9") (pinfunction "ADC0_DP0_9") (pintype "bidirectional"))
    )
    (net (code "80") (name "unconnected-(IC1-ADC0_DP3-Pad11)") (class "Default")
      (node (ref "IC1") (pin "11") (pinfunction "ADC0_DP3_11") (pintype "bidirectional"))
    )
    (net (code "81") (name "unconnected-(IC1-PTA4-Pad26)") (class "Default")
      (node (ref "IC1") (pin "26") (pinfunction "PTA4_26") (pintype "bidirectional"))
    )
    (net (code "82") (name "unconnected-(IC1-PTB19-Pad42)") (class "Default")
      (node (ref "IC1") (pin "42") (pinfunction "PTB19_42") (pintype "bidirectional"))
    )
    (net (code "83") (name "unconnected-(IC1-PTC9-Pad54)") (class "Default")
      (node (ref "IC1") (pin "54") (pinfunction "PTC9_54") (pintype "bidirectional"))
    )
    (net (code "84") (name "unconnected-(IC1-VREF_OUT-Pad17)") (class "Default")
      (node (ref "IC1") (pin "17") (pinfunction "VREF_OUT_17") (pintype "bidirectional"))
    )
    (net (code "85") (name "unconnected-(IC3A-B1-Pad18)") (class "Default")
      (node (ref "IC3") (pin "18") (pinfunction "B1_18") (pintype "bidirectional"))
    )
    (net (code "86") (name "unconnected-(IC3A-B2-Pad17)") (class "Default")
      (node (ref "IC3") (pin "17") (pinfunction "B2_17") (pintype "bidirectional"))
    )
    (net (code "87") (name "unconnected-(IC3A-B3-Pad16)") (class "Default")
      (node (ref "IC3") (pin "16") (pinfunction "B3_16") (pintype "bidirectional"))
    )
    (net (code "88") (name "unconnected-(J3-PadRSH)") (class "Default")
      (node (ref "J3") (pin "RSH") (pinfunction "RSH_RSH") (pintype "bidirectional"))
    )
    (net (code "89") (name "unconnected-(J3-PadTSH)") (class "Default")
      (node (ref "J3") (pin "TSH") (pinfunction "TSH_TSH") (pintype "bidirectional"))
    )
    (net (code "90") (name "unconnected-(J6-CARD_DETECT-PadCD1)") (class "Default")
      (node (ref "J6") (pin "CD1") (pinfunction "CARD_DETECT_CD1") (pintype "passive"))
    )
    (net (code "91") (name "unconnected-(J6-CARD_DETECT1-PadCD2)") (class "Default")
      (node (ref "J6") (pin "CD2") (pinfunction "CARD_DETECT1_CD2") (pintype "passive"))
    )
    (net (code "92") (name "unconnected-(J6-DAT1-Pad8)") (class "Default")
      (node (ref "J6") (pin "8") (pinfunction "DAT1_8") (pintype "bidirectional"))
    )
    (net (code "93") (name "unconnected-(J6-DAT2-Pad1)") (class "Default")
      (node (ref "J6") (pin "1") (pinfunction "DAT2_1") (pintype "bidirectional"))
    )
  )
)
